# myjtag.net
KiCad netlist of a schematic drawn in Altium Designer
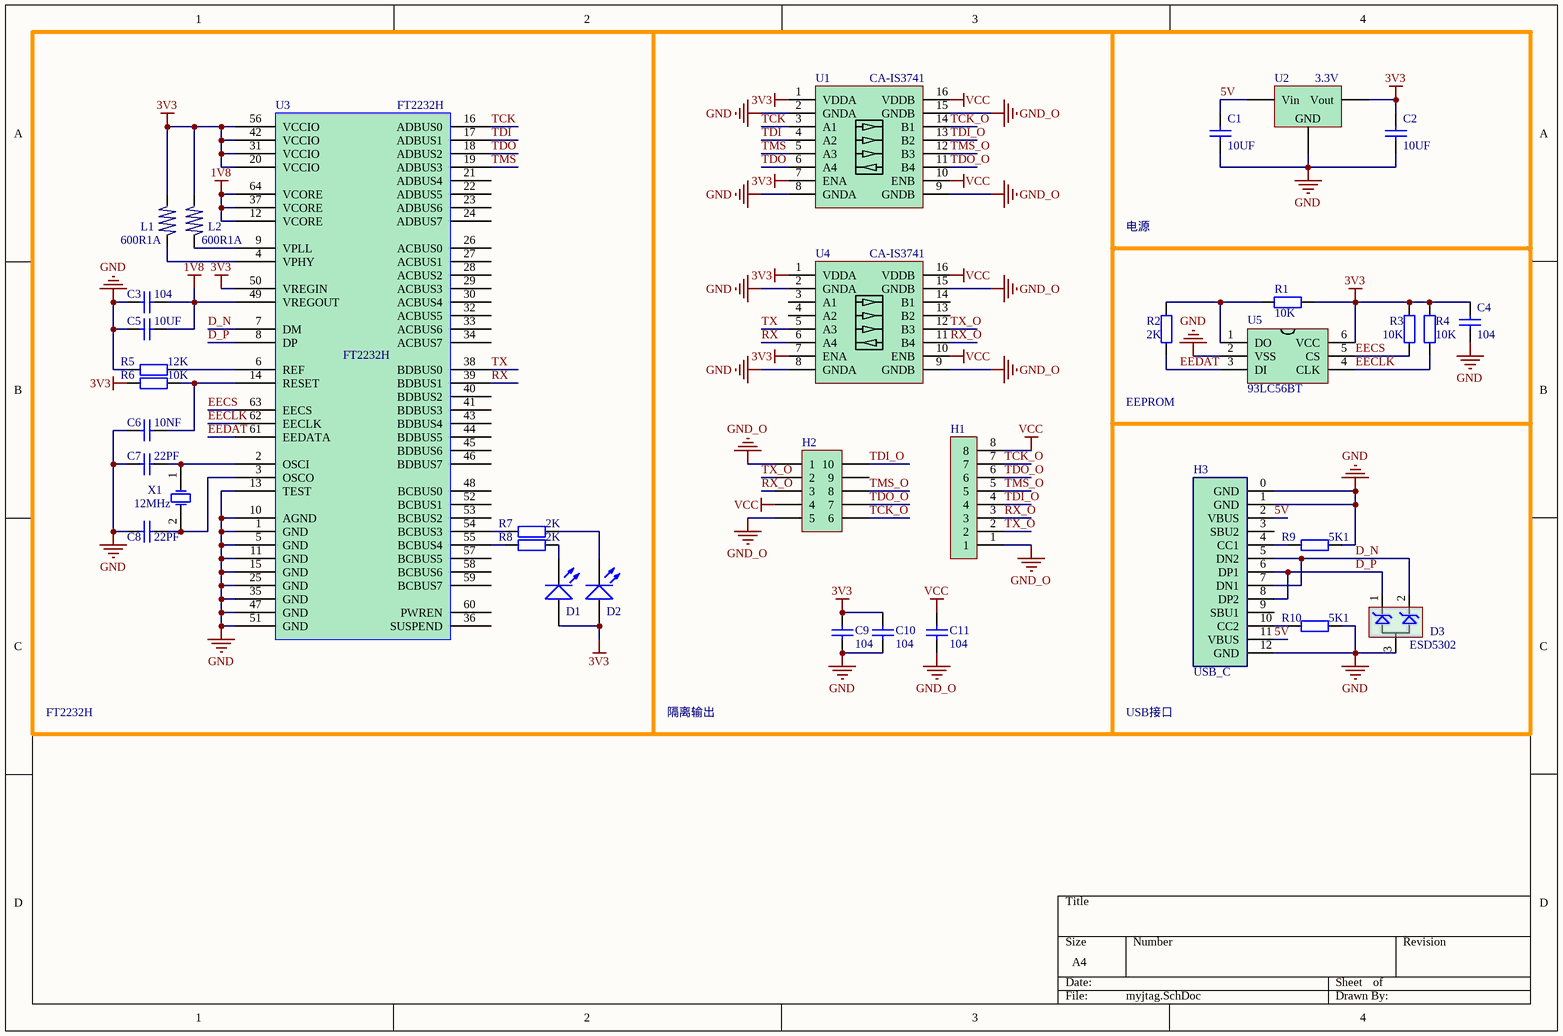
[diagram p0: myjtag.SchDoc]

(export (version "E")
  (design (tool "Eeschema 10.0.6"))
  (components
    (comp (ref "C1") (value "10UF") (footprint "0603_C") (libsource (lib "MT_Device") (part "0603_CAP")))
    (comp (ref "C2") (value "10UF") (footprint "0603_C") (libsource (lib "MT_Device") (part "0603_CAP")))
    (comp (ref "C3") (value "104") (footprint "0603_C") (libsource (lib "MT_Device") (part "0603_CAP")))
    (comp (ref "C4") (value "104") (footprint "0603_C") (libsource (lib "MT_Device") (part "0603_CAP")))
    (comp (ref "C5") (value "10UF") (footprint "0603_C") (libsource (lib "MT_Device") (part "0603_CAP")))
    (comp (ref "C6") (value "10NF") (footprint "0603_C") (libsource (lib "MT_Device") (part "0603_CAP")))
    (comp (ref "C7") (value "22PF") (footprint "0603_C") (libsource (lib "MT_Device") (part "0603_CAP")))
    (comp (ref "C8") (value "22PF") (footprint "0603_C") (libsource (lib "MT_Device") (part "0603_CAP")))
    (comp (ref "C9") (value "104") (footprint "0603_C") (libsource (lib "MT_Device") (part "0603_CAP")))
    (comp (ref "C10") (value "104") (footprint "0603_C") (libsource (lib "MT_Device") (part "0603_CAP")))
    (comp (ref "C11") (value "104") (footprint "0603_C") (libsource (lib "MT_Device") (part "0603_CAP")))
    (comp (ref "D1")
      (value "0603_LED")
      (footprint "0603_LED")
      (libsource (lib "MT_Device") (part "0603_LED"))
    )
    (comp (ref "D2")
      (value "0603_LED")
      (footprint "0603_LED")
      (libsource (lib "MT_Device") (part "0603_LED"))
    )
    (comp (ref "D3")
      (value "ESD5302")
      (footprint "SOT23")
      (description "ESD DIODE")
      (libsource (lib "MT_Device") (part "PESD5V2S2UT"))
    )
    (comp (ref "H1")
      (value "SH1.25mm_8P")
      (footprint "SH1.25MM_8P")
      (libsource (lib "MT_Connector") (part "SH1.25mm_8P"))
    )
    (comp (ref "H2")
      (value "Header_2.54_5P_2")
      (footprint "HDR2_5P")
      (libsource (lib "MT_Connector") (part "Header_2.54_5P_2"))
    )
    (comp (ref "H3")
      (value "USB_C")
      (footprint "USB_C_16PIN_SMT")
      (libsource (lib "MT_Device") (part "USB_C_16P_SMT"))
    )
    (comp (ref "L1")
      (value "600R1A")
      (footprint "0603_R")
      (description "Bead core")
      (libsource (lib "MT_Device") (part "0603_BeadCore"))
    )
    (comp (ref "L2")
      (value "600R1A")
      (footprint "0603_R")
      (description "Bead core")
      (libsource (lib "MT_Device") (part "0603_BeadCore"))
    )
    (comp (ref "R1") (value "10K") (footprint "0603_R") (libsource (lib "") (part "0603_RES_1")))
    (comp (ref "R2") (value "2K") (footprint "0603_R") (libsource (lib "MT_Device") (part "0603_RES")))
    (comp (ref "R3") (value "10K") (footprint "0603_R") (libsource (lib "MT_Device") (part "0603_RES")))
    (comp (ref "R4") (value "10K") (footprint "0603_R") (libsource (lib "MT_Device") (part "0603_RES")))
    (comp (ref "R5") (value "12K") (footprint "0603_R") (libsource (lib "") (part "0603_RES_1")))
    (comp (ref "R6") (value "10K") (footprint "0603_R") (libsource (lib "") (part "0603_RES_1")))
    (comp (ref "R7") (value "2K") (footprint "0603_R") (libsource (lib "") (part "0603_RES_1")))
    (comp (ref "R8") (value "2K") (footprint "0603_R") (libsource (lib "") (part "0603_RES_1")))
    (comp (ref "R9") (value "5K1") (footprint "0603_R") (libsource (lib "") (part "0603_RES_1")))
    (comp (ref "R10") (value "5K1") (footprint "0603_R") (libsource (lib "") (part "0603_RES_1")))
    (comp (ref "U1") (value "CA-IS3741") (footprint "SOIC16N") (libsource (lib "MT_Chip") (part "CA-IS3741")))
    (comp (ref "U2")
      (value "3.3V")
      (footprint "SOT23")
      (description "线性稳压器")
      (libsource (lib "MT_Device") (part "LDO_XC6206P332MR"))
    )
    (comp (ref "U3") (value "FT2232H") (footprint "LQFP64") (libsource (lib "MT_Chip") (part "FT2232H")))
    (comp (ref "U4") (value "CA-IS3741") (footprint "SOIC16N") (libsource (lib "MT_Chip") (part "CA-IS3741")))
    (comp (ref "U5") (value "93LC56BT") (footprint "SOT_23_6") (libsource (lib "MT_Chip") (part "93LC56BT")))
    (comp (ref "X1")
      (value "12MHz")
      (footprint "XTAL_5032")
      (description "贴片无源晶振")
      (libsource (lib "MT_Device") (part "XTAL_5032"))
    )
  )
  (nets
    (net (code "1") (name "/5V") (class "Default")
      (node (ref "C1") (pin "2") (pinfunction "2_2") (pintype "passive"))
      (node (ref "H3") (pin "11") (pinfunction "VBUS_11") (pintype "passive"))
      (node (ref "H3") (pin "2") (pinfunction "VBUS_2") (pintype "passive"))
      (node (ref "U2") (pin "3") (pinfunction "Vin_3") (pintype "passive"))
    )
    (net (code "2") (name "/D_N") (class "Default")
      (node (ref "D3") (pin "2") (pinfunction "2_2") (pintype "passive"))
      (node (ref "H3") (pin "5") (pinfunction "DN2_5") (pintype "passive"))
      (node (ref "H3") (pin "7") (pinfunction "DN1_7") (pintype "passive"))
      (node (ref "U3") (pin "7") (pinfunction "DM_7") (pintype "passive"))
    )
    (net (code "3") (name "/D_P") (class "Default")
      (node (ref "D3") (pin "1") (pinfunction "1_1") (pintype "passive"))
      (node (ref "H3") (pin "6") (pinfunction "DP1_6") (pintype "passive"))
      (node (ref "H3") (pin "8") (pinfunction "DP2_8") (pintype "passive"))
      (node (ref "U3") (pin "8") (pinfunction "DP_8") (pintype "passive"))
    )
    (net (code "4") (name "/EECLK") (class "Default")
      (node (ref "R4") (pin "2") (pinfunction "2_2") (pintype "passive"))
      (node (ref "U3") (pin "62") (pinfunction "EECLK_62") (pintype "passive"))
      (node (ref "U5") (pin "4") (pinfunction "CLK_4") (pintype "passive"))
    )
    (net (code "5") (name "/EECS") (class "Default")
      (node (ref "R3") (pin "2") (pinfunction "2_2") (pintype "passive"))
      (node (ref "U3") (pin "63") (pinfunction "EECS_63") (pintype "passive"))
      (node (ref "U5") (pin "5") (pinfunction "CS_5") (pintype "passive"))
    )
    (net (code "6") (name "/EEDAT") (class "Default")
      (node (ref "R2") (pin "2") (pinfunction "2_2") (pintype "passive"))
      (node (ref "U3") (pin "61") (pinfunction "EEDATA_61") (pintype "passive"))
      (node (ref "U5") (pin "3") (pinfunction "DI_3") (pintype "passive"))
    )
    (net (code "7") (name "/RX") (class "Default")
      (node (ref "U3") (pin "39") (pinfunction "BDBUS1_39") (pintype "passive"))
      (node (ref "U4") (pin "6") (pinfunction "A4_6") (pintype "passive"))
    )
    (net (code "8") (name "/RX_O") (class "Default")
      (node (ref "H1") (pin "3") (pinfunction "3_3") (pintype "passive"))
      (node (ref "H2") (pin "3") (pinfunction "3_3") (pintype "passive"))
      (node (ref "U4") (pin "11") (pinfunction "B4_11") (pintype "passive"))
    )
    (net (code "9") (name "/TCK") (class "Default")
      (node (ref "U1") (pin "3") (pinfunction "A1_3") (pintype "passive"))
      (node (ref "U3") (pin "16") (pinfunction "ADBUS0_16") (pintype "passive"))
    )
    (net (code "10") (name "/TCK_O") (class "Default")
      (node (ref "H1") (pin "7") (pinfunction "7_7") (pintype "passive"))
      (node (ref "H2") (pin "6") (pinfunction "6_6") (pintype "passive"))
      (node (ref "U1") (pin "14") (pinfunction "B1_14") (pintype "passive"))
    )
    (net (code "11") (name "/TDI") (class "Default")
      (node (ref "U1") (pin "4") (pinfunction "A2_4") (pintype "passive"))
      (node (ref "U3") (pin "17") (pinfunction "ADBUS1_17") (pintype "passive"))
    )
    (net (code "12") (name "/TDI_O") (class "Default")
      (node (ref "H1") (pin "4") (pinfunction "4_4") (pintype "passive"))
      (node (ref "H2") (pin "10") (pinfunction "10_10") (pintype "passive"))
      (node (ref "U1") (pin "13") (pinfunction "B2_13") (pintype "passive"))
    )
    (net (code "13") (name "/TDO") (class "Default")
      (node (ref "U1") (pin "6") (pinfunction "A4_6") (pintype "passive"))
      (node (ref "U3") (pin "18") (pinfunction "ADBUS2_18") (pintype "passive"))
    )
    (net (code "14") (name "/TDO_O") (class "Default")
      (node (ref "H1") (pin "6") (pinfunction "6_6") (pintype "passive"))
      (node (ref "H2") (pin "7") (pinfunction "7_7") (pintype "passive"))
      (node (ref "U1") (pin "11") (pinfunction "B4_11") (pintype "passive"))
    )
    (net (code "15") (name "/TMS") (class "Default")
      (node (ref "U1") (pin "5") (pinfunction "A3_5") (pintype "passive"))
      (node (ref "U3") (pin "19") (pinfunction "ADBUS3_19") (pintype "passive"))
    )
    (net (code "16") (name "/TMS_O") (class "Default")
      (node (ref "H1") (pin "5") (pinfunction "5_5") (pintype "passive"))
      (node (ref "H2") (pin "8") (pinfunction "8_8") (pintype "passive"))
      (node (ref "U1") (pin "12") (pinfunction "B3_12") (pintype "passive"))
    )
    (net (code "17") (name "/TX") (class "Default")
      (node (ref "U3") (pin "38") (pinfunction "BDBUS0_38") (pintype "passive"))
      (node (ref "U4") (pin "5") (pinfunction "A3_5") (pintype "passive"))
    )
    (net (code "18") (name "/TX_O") (class "Default")
      (node (ref "H1") (pin "2") (pinfunction "2_2") (pintype "passive"))
      (node (ref "H2") (pin "2") (pinfunction "2_2") (pintype "passive"))
      (node (ref "U4") (pin "12") (pinfunction "B3_12") (pintype "passive"))
    )
    (net (code "19") (name "1V8") (class "Default")
      (node (ref "C3") (pin "2") (pinfunction "2_2") (pintype "passive"))
      (node (ref "C5") (pin "2") (pinfunction "2_2") (pintype "passive"))
      (node (ref "U3") (pin "12") (pinfunction "VCORE_12") (pintype "passive"))
      (node (ref "U3") (pin "37") (pinfunction "VCORE_37") (pintype "passive"))
      (node (ref "U3") (pin "49") (pinfunction "VREGOUT_49") (pintype "passive"))
      (node (ref "U3") (pin "64") (pinfunction "VCORE_64") (pintype "passive"))
    )
    (net (code "20") (name "3V3") (class "Default")
      (node (ref "C10") (pin "2") (pinfunction "2_2") (pintype "passive"))
      (node (ref "C2") (pin "2") (pinfunction "2_2") (pintype "passive"))
      (node (ref "C4") (pin "1") (pinfunction "1_1") (pintype "passive"))
      (node (ref "C9") (pin "2") (pinfunction "2_2") (pintype "passive"))
      (node (ref "D1") (pin "A") (pinfunction "A_A") (pintype "passive"))
      (node (ref "D2") (pin "A") (pinfunction "A_A") (pintype "passive"))
      (node (ref "L1") (pin "2") (pintype "passive"))
      (node (ref "L2") (pin "2") (pintype "passive"))
      (node (ref "R1") (pin "1") (pinfunction "1_1") (pintype "passive"))
      (node (ref "R3") (pin "1") (pinfunction "1_1") (pintype "passive"))
      (node (ref "R4") (pin "1") (pinfunction "1_1") (pintype "passive"))
      (node (ref "R6") (pin "2") (pinfunction "2_2") (pintype "passive"))
      (node (ref "U1") (pin "1") (pinfunction "VDDA_1") (pintype "passive"))
      (node (ref "U1") (pin "7") (pinfunction "ENA_7") (pintype "passive"))
      (node (ref "U2") (pin "2") (pinfunction "Vout_2") (pintype "passive"))
      (node (ref "U3") (pin "20") (pinfunction "VCCIO_20") (pintype "passive"))
      (node (ref "U3") (pin "31") (pinfunction "VCCIO_31") (pintype "passive"))
      (node (ref "U3") (pin "42") (pinfunction "VCCIO_42") (pintype "passive"))
      (node (ref "U3") (pin "50") (pinfunction "VREGIN_50") (pintype "passive"))
      (node (ref "U3") (pin "56") (pinfunction "VCCIO_56") (pintype "passive"))
      (node (ref "U4") (pin "1") (pinfunction "VDDA_1") (pintype "passive"))
      (node (ref "U4") (pin "7") (pinfunction "ENA_7") (pintype "passive"))
      (node (ref "U5") (pin "6") (pinfunction "VCC_6") (pintype "passive"))
    )
    (net (code "21") (name "GND") (class "Default")
      (node (ref "C1") (pin "1") (pinfunction "1_1") (pintype "passive"))
      (node (ref "C10") (pin "1") (pinfunction "1_1") (pintype "passive"))
      (node (ref "C2") (pin "1") (pinfunction "1_1") (pintype "passive"))
      (node (ref "C3") (pin "1") (pinfunction "1_1") (pintype "passive"))
      (node (ref "C4") (pin "2") (pinfunction "2_2") (pintype "passive"))
      (node (ref "C5") (pin "1") (pinfunction "1_1") (pintype "passive"))
      (node (ref "C6") (pin "1") (pinfunction "1_1") (pintype "passive"))
      (node (ref "C7") (pin "1") (pinfunction "1_1") (pintype "passive"))
      (node (ref "C8") (pin "1") (pinfunction "1_1") (pintype "passive"))
      (node (ref "C9") (pin "1") (pinfunction "1_1") (pintype "passive"))
      (node (ref "D3") (pin "3") (pinfunction "3_3") (pintype "passive"))
      (node (ref "H3") (pin "0") (pinfunction "GND_0") (pintype "passive"))
      (node (ref "H3") (pin "1") (pinfunction "GND_1") (pintype "passive"))
      (node (ref "H3") (pin "12") (pinfunction "GND_12") (pintype "passive"))
      (node (ref "R10") (pin "1") (pinfunction "1_1") (pintype "passive"))
      (node (ref "R5") (pin "2") (pinfunction "2_2") (pintype "passive"))
      (node (ref "R9") (pin "1") (pinfunction "1_1") (pintype "passive"))
      (node (ref "U1") (pin "2") (pinfunction "GNDA_2") (pintype "passive"))
      (node (ref "U1") (pin "8") (pinfunction "GNDA_8") (pintype "passive"))
      (node (ref "U2") (pin "1") (pinfunction "GND_1") (pintype "passive"))
      (node (ref "U3") (pin "1") (pinfunction "GND_1") (pintype "passive"))
      (node (ref "U3") (pin "10") (pinfunction "AGND_10") (pintype "passive"))
      (node (ref "U3") (pin "11") (pinfunction "GND_11") (pintype "passive"))
      (node (ref "U3") (pin "13") (pinfunction "TEST_13") (pintype "passive"))
      (node (ref "U3") (pin "15") (pinfunction "GND_15") (pintype "passive"))
      (node (ref "U3") (pin "25") (pinfunction "GND_25") (pintype "passive"))
      (node (ref "U3") (pin "35") (pinfunction "GND_35") (pintype "passive"))
      (node (ref "U3") (pin "47") (pinfunction "GND_47") (pintype "passive"))
      (node (ref "U3") (pin "5") (pinfunction "GND_5") (pintype "passive"))
      (node (ref "U3") (pin "51") (pinfunction "GND_51") (pintype "passive"))
      (node (ref "U4") (pin "2") (pinfunction "GNDA_2") (pintype "passive"))
      (node (ref "U4") (pin "8") (pinfunction "GNDA_8") (pintype "passive"))
      (node (ref "U5") (pin "2") (pinfunction "VSS_2") (pintype "passive"))
    )
    (net (code "22") (name "GND_O") (class "Default")
      (node (ref "C11") (pin "1") (pinfunction "1_1") (pintype "passive"))
      (node (ref "H1") (pin "1") (pinfunction "1_1") (pintype "passive"))
      (node (ref "H2") (pin "1") (pinfunction "1_1") (pintype "passive"))
      (node (ref "H2") (pin "5") (pinfunction "5_5") (pintype "passive"))
      (node (ref "U1") (pin "15") (pinfunction "GNDB_15") (pintype "passive"))
      (node (ref "U1") (pin "9") (pinfunction "GNDB_9") (pintype "passive"))
      (node (ref "U4") (pin "15") (pinfunction "GNDB_15") (pintype "passive"))
      (node (ref "U4") (pin "9") (pinfunction "GNDB_9") (pintype "passive"))
    )
    (net (code "23") (name "Net-(D1-PadK)") (class "Default")
      (node (ref "D1") (pin "K") (pinfunction "K_K") (pintype "passive"))
      (node (ref "R8") (pin "1") (pinfunction "1_1") (pintype "passive"))
    )
    (net (code "24") (name "Net-(D2-PadK)") (class "Default")
      (node (ref "D2") (pin "K") (pinfunction "K_K") (pintype "passive"))
      (node (ref "R7") (pin "1") (pinfunction "1_1") (pintype "passive"))
    )
    (net (code "25") (name "Net-(H3-CC1)") (class "Default")
      (node (ref "H3") (pin "4") (pinfunction "CC1_4") (pintype "passive"))
      (node (ref "R9") (pin "2") (pinfunction "2_2") (pintype "passive"))
    )
    (net (code "26") (name "Net-(H3-CC2)") (class "Default")
      (node (ref "H3") (pin "10") (pinfunction "CC2_10") (pintype "passive"))
      (node (ref "R10") (pin "2") (pinfunction "2_2") (pintype "passive"))
    )
    (net (code "27") (name "Net-(U3-BCBUS3)") (class "Default")
      (node (ref "R7") (pin "2") (pinfunction "2_2") (pintype "passive"))
      (node (ref "U3") (pin "54") (pinfunction "BCBUS3_54") (pintype "passive"))
    )
    (net (code "28") (name "Net-(U3-BCBUS4)") (class "Default")
      (node (ref "R8") (pin "2") (pinfunction "2_2") (pintype "passive"))
      (node (ref "U3") (pin "55") (pinfunction "BCBUS4_55") (pintype "passive"))
    )
    (net (code "29") (name "Net-(U3-OSCI)") (class "Default")
      (node (ref "C7") (pin "2") (pinfunction "2_2") (pintype "passive"))
      (node (ref "U3") (pin "2") (pinfunction "OSCI_2") (pintype "passive"))
      (node (ref "X1") (pin "1") (pinfunction "OSC1_1") (pintype "passive"))
    )
    (net (code "30") (name "Net-(U3-OSCO)") (class "Default")
      (node (ref "C8") (pin "2") (pinfunction "2_2") (pintype "passive"))
      (node (ref "U3") (pin "3") (pinfunction "OSCO_3") (pintype "passive"))
      (node (ref "X1") (pin "2") (pinfunction "OSC2_2") (pintype "passive"))
    )
    (net (code "31") (name "Net-(U3-REF)") (class "Default")
      (node (ref "R5") (pin "1") (pinfunction "1_1") (pintype "passive"))
      (node (ref "U3") (pin "6") (pinfunction "REF_6") (pintype "passive"))
    )
    (net (code "32") (name "Net-(U3-RESET)") (class "Default")
      (node (ref "C6") (pin "2") (pinfunction "2_2") (pintype "passive"))
      (node (ref "R6") (pin "1") (pinfunction "1_1") (pintype "passive"))
      (node (ref "U3") (pin "14") (pinfunction "RESET_14") (pintype "passive"))
    )
    (net (code "33") (name "Net-(U3-VPHY)") (class "Default")
      (node (ref "L1") (pin "1") (pintype "passive"))
      (node (ref "U3") (pin "4") (pinfunction "VPHY_4") (pintype "passive"))
    )
    (net (code "34") (name "Net-(U3-VPLL)") (class "Default")
      (node (ref "L2") (pin "1") (pintype "passive"))
      (node (ref "U3") (pin "9") (pinfunction "VPLL_9") (pintype "passive"))
    )
    (net (code "35") (name "Net-(U5-DO)") (class "Default")
      (node (ref "R1") (pin "2") (pinfunction "2_2") (pintype "passive"))
      (node (ref "R2") (pin "1") (pinfunction "1_1") (pintype "passive"))
      (node (ref "U5") (pin "1") (pinfunction "DO_1") (pintype "passive"))
    )
    (net (code "36") (name "VCC") (class "Default")
      (node (ref "C11") (pin "2") (pinfunction "2_2") (pintype "passive"))
      (node (ref "H1") (pin "8") (pinfunction "8_8") (pintype "passive"))
      (node (ref "H2") (pin "4") (pinfunction "4_4") (pintype "passive"))
      (node (ref "U1") (pin "10") (pinfunction "ENB_10") (pintype "passive"))
      (node (ref "U1") (pin "16") (pinfunction "VDDB_16") (pintype "passive"))
      (node (ref "U4") (pin "10") (pinfunction "ENB_10") (pintype "passive"))
      (node (ref "U4") (pin "16") (pinfunction "VDDB_16") (pintype "passive"))
    )
    (net (code "37") (name "unconnected-(H2-Pad9)") (class "Default")
      (node (ref "H2") (pin "9") (pinfunction "9_9") (pintype "passive"))
    )
    (net (code "38") (name "unconnected-(H3-SBU1-Pad9)") (class "Default")
      (node (ref "H3") (pin "9") (pinfunction "SBU1_9") (pintype "passive"))
    )
    (net (code "39") (name "unconnected-(H3-SBU2-Pad3)") (class "Default")
      (node (ref "H3") (pin "3") (pinfunction "SBU2_3") (pintype "passive"))
    )
    (net (code "40") (name "unconnected-(U3-ACBUS0-Pad26)") (class "Default")
      (node (ref "U3") (pin "26") (pinfunction "ACBUS0_26") (pintype "passive"))
    )
    (net (code "41") (name "unconnected-(U3-ACBUS1-Pad27)") (class "Default")
      (node (ref "U3") (pin "27") (pinfunction "ACBUS1_27") (pintype "passive"))
    )
    (net (code "42") (name "unconnected-(U3-ACBUS2-Pad28)") (class "Default")
      (node (ref "U3") (pin "28") (pinfunction "ACBUS2_28") (pintype "passive"))
    )
    (net (code "43") (name "unconnected-(U3-ACBUS3-Pad29)") (class "Default")
      (node (ref "U3") (pin "29") (pinfunction "ACBUS3_29") (pintype "passive"))
    )
    (net (code "44") (name "unconnected-(U3-ACBUS4-Pad30)") (class "Default")
      (node (ref "U3") (pin "30") (pinfunction "ACBUS4_30") (pintype "passive"))
    )
    (net (code "45") (name "unconnected-(U3-ACBUS5-Pad32)") (class "Default")
      (node (ref "U3") (pin "32") (pinfunction "ACBUS5_32") (pintype "passive"))
    )
    (net (code "46") (name "unconnected-(U3-ACBUS6-Pad33)") (class "Default")
      (node (ref "U3") (pin "33") (pinfunction "ACBUS6_33") (pintype "passive"))
    )
    (net (code "47") (name "unconnected-(U3-ACBUS7-Pad34)") (class "Default")
      (node (ref "U3") (pin "34") (pinfunction "ACBUS7_34") (pintype "passive"))
    )
    (net (code "48") (name "unconnected-(U3-ADBUS4-Pad21)") (class "Default")
      (node (ref "U3") (pin "21") (pinfunction "ADBUS4_21") (pintype "passive"))
    )
    (net (code "49") (name "unconnected-(U3-ADBUS5-Pad22)") (class "Default")
      (node (ref "U3") (pin "22") (pinfunction "ADBUS5_22") (pintype "passive"))
    )
    (net (code "50") (name "unconnected-(U3-ADBUS6-Pad23)") (class "Default")
      (node (ref "U3") (pin "23") (pinfunction "ADBUS6_23") (pintype "passive"))
    )
    (net (code "51") (name "unconnected-(U3-ADBUS7-Pad24)") (class "Default")
      (node (ref "U3") (pin "24") (pinfunction "ADBUS7_24") (pintype "passive"))
    )
    (net (code "52") (name "unconnected-(U3-BCBUS0-Pad48)") (class "Default")
      (node (ref "U3") (pin "48") (pinfunction "BCBUS0_48") (pintype "passive"))
    )
    (net (code "53") (name "unconnected-(U3-BCBUS1-Pad52)") (class "Default")
      (node (ref "U3") (pin "52") (pinfunction "BCBUS1_52") (pintype "passive"))
    )
    (net (code "54") (name "unconnected-(U3-BCBUS2-Pad53)") (class "Default")
      (node (ref "U3") (pin "53") (pinfunction "BCBUS2_53") (pintype "passive"))
    )
    (net (code "55") (name "unconnected-(U3-BCBUS5-Pad57)") (class "Default")
      (node (ref "U3") (pin "57") (pinfunction "BCBUS5_57") (pintype "passive"))
    )
    (net (code "56") (name "unconnected-(U3-BCBUS6-Pad58)") (class "Default")
      (node (ref "U3") (pin "58") (pinfunction "BCBUS6_58") (pintype "passive"))
    )
    (net (code "57") (name "unconnected-(U3-BCBUS7-Pad59)") (class "Default")
      (node (ref "U3") (pin "59") (pinfunction "BCBUS7_59") (pintype "passive"))
    )
    (net (code "58") (name "unconnected-(U3-BDBUS2-Pad40)") (class "Default")
      (node (ref "U3") (pin "40") (pinfunction "BDBUS2_40") (pintype "passive"))
    )
    (net (code "59") (name "unconnected-(U3-BDBUS3-Pad41)") (class "Default")
      (node (ref "U3") (pin "41") (pinfunction "BDBUS3_41") (pintype "passive"))
    )
    (net (code "60") (name "unconnected-(U3-BDBUS4-Pad43)") (class "Default")
      (node (ref "U3") (pin "43") (pinfunction "BDBUS4_43") (pintype "passive"))
    )
    (net (code "61") (name "unconnected-(U3-BDBUS5-Pad44)") (class "Default")
      (node (ref "U3") (pin "44") (pinfunction "BDBUS5_44") (pintype "passive"))
    )
    (net (code "62") (name "unconnected-(U3-BDBUS6-Pad45)") (class "Default")
      (node (ref "U3") (pin "45") (pinfunction "BDBUS6_45") (pintype "passive"))
    )
    (net (code "63") (name "unconnected-(U3-BDBUS7-Pad46)") (class "Default")
      (node (ref "U3") (pin "46") (pinfunction "BDBUS7_46") (pintype "passive"))
    )
    (net (code "64") (name "unconnected-(U3-PWREN-Pad60)") (class "Default")
      (node (ref "U3") (pin "60") (pinfunction "PWREN_60") (pintype "passive"))
    )
    (net (code "65") (name "unconnected-(U3-SUSPEND-Pad36)") (class "Default")
      (node (ref "U3") (pin "36") (pinfunction "SUSPEND_36") (pintype "passive"))
    )
    (net (code "66") (name "unconnected-(U4-A1-Pad3)") (class "Default")
      (node (ref "U4") (pin "3") (pinfunction "A1_3") (pintype "passive"))
    )
    (net (code "67") (name "unconnected-(U4-A2-Pad4)") (class "Default")
      (node (ref "U4") (pin "4") (pinfunction "A2_4") (pintype "passive"))
    )
    (net (code "68") (name "unconnected-(U4-B1-Pad14)") (class "Default")
      (node (ref "U4") (pin "14") (pinfunction "B1_14") (pintype "passive"))
    )
    (net (code "69") (name "unconnected-(U4-B2-Pad13)") (class "Default")
      (node (ref "U4") (pin "13") (pinfunction "B2_13") (pintype "passive"))
    )
  )
)
